# adapter_sch.net
KiCad netlist of a schematic drawn in Altium Designer
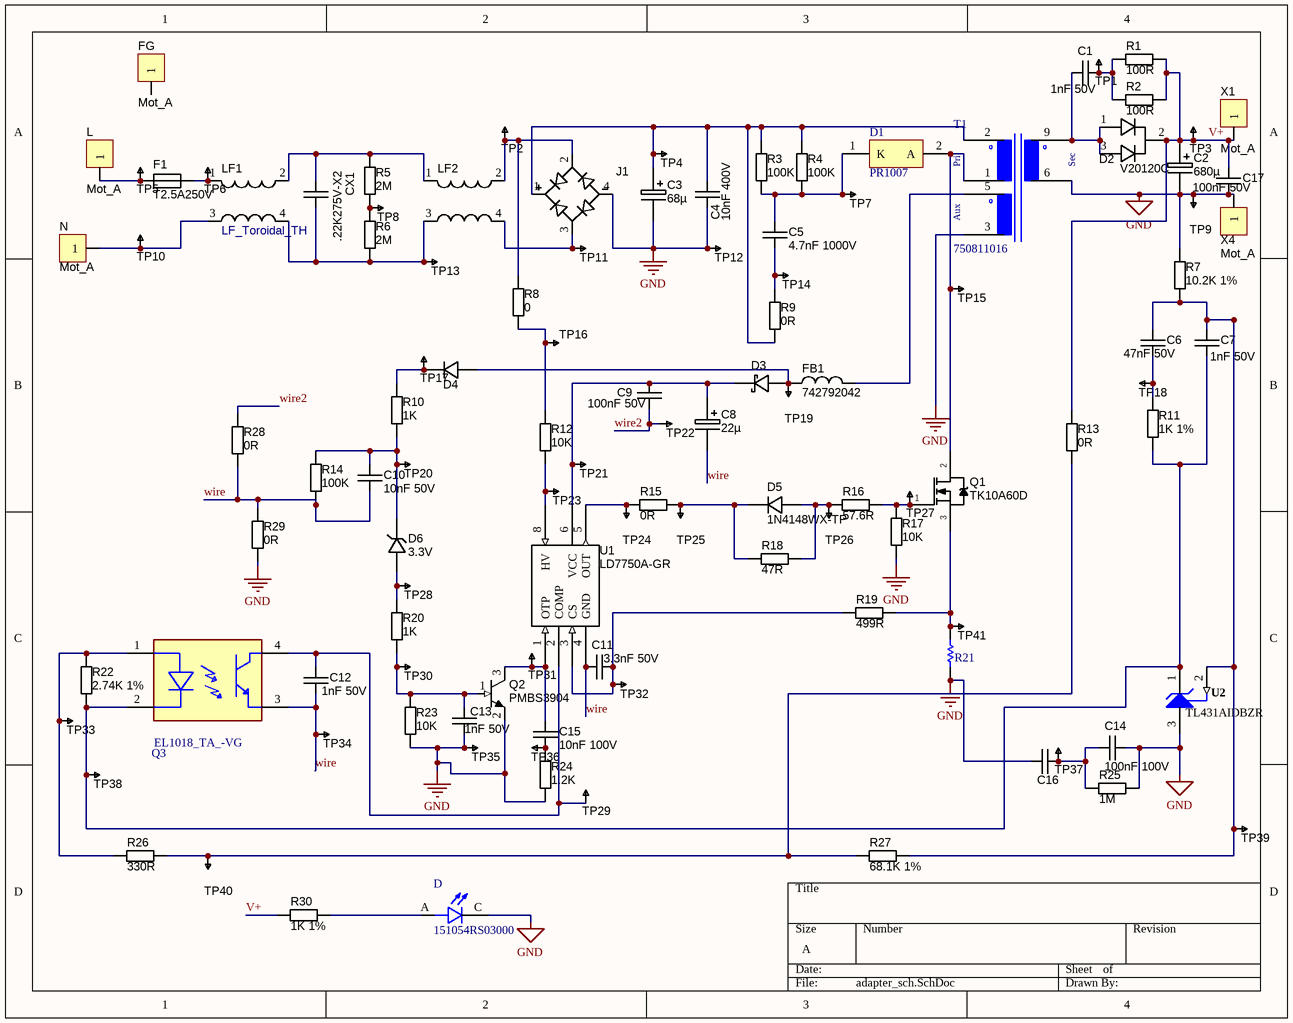
[diagram p0: adapter_sch.SchDoc]

(export (version "E")
  (design (tool "Eeschema 10.0.6"))
  (components
    (comp (ref "C1")
      (value "1nF 50V")
      (footprint "CAPC2012X135N")
      (description "Capacitor SMD Cer 4.7uF 10% 16V X5R 0805")
      (fields (field (name "TOLERANCE") "±10%") (field (name "Comment") "approved sub OK"))
      (libsource (lib "PBL - Capacitors") (part "CAPC_4u7_0805"))
    )
    (comp (ref "C2")
      (value "680µ")
      (footprint "CAPE4.7MM_Rad_10x17mm")
      (description "Capacitor THT Alum Elec 680uF 25V")
      (fields (field (name "TOLERANCE") "±20%"))
      (libsource (lib "PBL - Capacitors") (part "CAPE_680u_25V_THT"))
    )
    (comp (ref "C3")
      (value "68µ")
      (footprint "CAPAE400V68uF16X25")
      (description "Capacitor THT Alum Elec 68uF 20% 400V")
      (fields (field (name "TOLERANCE") "±20%"))
      (libsource (lib "PBL - Capacitors") (part "CAPE_68u_400V_THT"))
    )
    (comp (ref "C4")
      (value "10nF 400V")
      (footprint "CAPC3216X180N")
      (description "Capacitor SMD Cer 10uF 10% 16V X7R 1206")
      (fields (field (name "TOLERANCE") "±10%") (field (name "Comment") "approved sub OK"))
      (libsource (lib "PBL - Capacitors") (part "CAPC_10u_1206_16V"))
    )
    (comp (ref "C5")
      (value "4.7nF 1000V")
      (footprint "CAPC3216X180N")
      (description "Capacitor SMD Cer 10uF 10% 16V X7R 1206")
      (fields (field (name "TOLERANCE") "±10%") (field (name "Comment") "approved sub OK"))
      (libsource (lib "PBL - Capacitors") (part "CAPC_10u_1206_16V"))
    )
    (comp (ref "C6")
      (value "47nF 50V")
      (footprint "CAPC1608X90N")
      (description "Capacitor SMD Cer 10pF 5% 50V NP0 0603")
      (fields (field (name "TOLERANCE") "±5%"))
      (libsource (lib "PBL - Capacitors") (part "CAPC_10p_0603_NP0_1%_50V"))
    )
    (comp (ref "C7")
      (value "1nF 50V")
      (footprint "CAPC1608X90N")
      (description "Capacitor SMD Cer 10pF 5% 50V NP0 0603")
      (fields (field (name "TOLERANCE") "±5%"))
      (libsource (lib "PBL - Capacitors") (part "CAPC_10p_0603_NP0_1%_50V"))
    )
    (comp (ref "C8")
      (value "22µ")
      (footprint "CAPE2MM_Rad_5x11mm")
      (description "Capacitor THT Alum Elec 22uF 50V")
      (fields (field (name "TOLERANCE") "±20%"))
      (libsource (lib "PBL - Capacitors") (part "CAPE_22u_50V_THT"))
    )
    (comp (ref "C9")
      (value "100nF 50V")
      (footprint "CAPC1608X90N")
      (description "Capacitor SMD Cer 10pF 5% 50V NP0 0603")
      (fields (field (name "TOLERANCE") "±5%"))
      (libsource (lib "PBL - Capacitors") (part "CAPC_10p_0603_NP0_1%_50V"))
    )
    (comp (ref "C10")
      (value "10nF 50V")
      (footprint "CAPC1608X90N")
      (description "Capacitor SMD Cer 10pF 5% 50V NP0 0603")
      (fields (field (name "TOLERANCE") "±5%"))
      (libsource (lib "PBL - Capacitors") (part "CAPC_10p_0603_NP0_1%_50V"))
    )
    (comp (ref "C11")
      (value "3.3nF 50V")
      (footprint "CAPC1608X90N")
      (description "Capacitor SMD Cer 10pF 5% 50V NP0 0603")
      (fields (field (name "TOLERANCE") "±5%"))
      (libsource (lib "PBL - Capacitors") (part "CAPC_10p_0603_NP0_1%_50V"))
    )
    (comp (ref "C12")
      (value "1nF 50V")
      (footprint "CAPC1608X90N")
      (description "Capacitor SMD Cer 10pF 5% 50V NP0 0603")
      (fields (field (name "TOLERANCE") "±5%"))
      (libsource (lib "PBL - Capacitors") (part "CAPC_10p_0603_NP0_1%_50V"))
    )
    (comp (ref "C13")
      (value "1nF 50V")
      (footprint "CAPC1608X90N")
      (description "Capacitor SMD Cer 10pF 5% 50V NP0 0603")
      (fields (field (name "TOLERANCE") "±5%"))
      (libsource (lib "PBL - Capacitors") (part "CAPC_10p_0603_NP0_1%_50V"))
    )
    (comp (ref "C14")
      (value "100nF 100V")
      (footprint "CAPC3216X180N")
      (description "Capacitor SMD Cer 10uF 10% 16V X7R 1206")
      (fields (field (name "TOLERANCE") "±10%") (field (name "Comment") "approved sub OK"))
      (libsource (lib "PBL - Capacitors") (part "CAPC_10u_1206_16V"))
    )
    (comp (ref "C15")
      (value "10nF 100V")
      (footprint "CAPC1608X90N")
      (description "Capacitor SMD Cer 10pF 5% 50V NP0 0603")
      (fields (field (name "TOLERANCE") "±5%"))
      (libsource (lib "PBL - Capacitors") (part "CAPC_10p_0603_NP0_1%_50V"))
    )
    (comp (ref "C16")
      (value "~")
      (footprint "CAPR9.5_CC")
      (description "Capacitor THD Ceramic 4KV")
      (fields (field (name "TOLERANCE") "±10%"))
      (libsource (lib "PBL - Capacitors") (part "CAPC_4KVV_CR"))
    )
    (comp (ref "C17")
      (value "100nF 50V")
      (footprint "C0805")
      (description "Capacitor SMD Cer 4.7uF 10% 16V X5R 0805")
      (fields (field (name "TOLERANCE") "±10%") (field (name "Comment") "approved sub OK"))
      (libsource (lib "PBL - Capacitors") (part "CAPC_4u7_0805"))
    )
    (comp (ref "CX1")
      (value ".22K275V-X2")
      (footprint "CAPMPF0.22K275V-X2_0.22UF")
      (description "Safety Capacitor THD MP Film 22nF 10% 250V")
      (fields (field (name "TOLERANCE") "±10%"))
      (libsource (lib "PBL - Capacitors") (part "CAPMPF_22n_250V_MP"))
    )
    (comp (ref "D")
      (value "151054RS03000")
      (footprint "LED_151054RS03000")
      (description "Red 623nm LED Indication - Discrete 1.9V Radial")
      (fields (field (name "MF") "Wurth Electronics"))
      (libsource (lib "LED_Radial151054RS03000") (part "151054RS03000"))
    )
    (comp (ref "D1")
      (value "PR1007")
      (footprint "DO-41 - Bended Radial")
      (description "Fast Recovery Rectifier Diode, 2-Pin Axial_Lead, Pb-Free, Bulk Box")
      (fields (field (name "MANUFACTURER") "On Semiconductor") (field (name "PARTNUMBER") "1N4003FF"))
      (libsource (lib "Diodes") (part "PR1007"))
    )
    (comp (ref "D2")
      (value "DIODE_SCHOTTKY_V20120C_TH")
      (footprint "DIODE_SCHOTTKY_V20120C_TH")
      (description "SCHOTTKY RECTIFIER TO-220AB COMMON CATHODE THROUGH HOLE")
      (fields
        (field (name "MANUFACTURER") "Micro Commercial Co")
        (field (name "MANUFACTURER PART NUMBER") "V20120C")
      )
      (libsource (lib "PBL - Diodes") (part "DIODE_SCHOTTKY_V20120C_TH"))
    )
    (comp (ref "D3")
      (value "DIODE_SCHOTTKY_10MQ100NPBF")
      (footprint "DO-214AC")
      (description "Diode Schottky SMD 100V 2A SMA")
      (libsource (lib "PBL - Diodes") (part "DIODE_SCHOTTKY_10MQ100NPBF"))
    )
    (comp (ref "D4")
      (value "100V; 1.5A")
      (footprint "SOD123")
      (description "surface mount switching diode L1N4148WT1G")
      (libsource (lib "PBL - Diodes") (part "DIODE_switching_SJ_SOD_1-3"))
    )
    (comp (ref "D5")
      (value "DIODE_75V_500mW")
      (footprint "SOD323")
      (description "Diode SMD 300mA 0.5W SOD323")
      (fields
        (field (name "MANUFACTURER") "Micro Commercial Co")
        (field (name "MANUFACTURER PART NUMBER") "1N4148WX-TP")
      )
      (libsource (lib "PBL - Diodes") (part "DIODE_75V_500mW"))
    )
    (comp (ref "D6")
      (value "3.3V")
      (footprint "SOD323")
      (description "Diode Zener SMD 3.3V 200mW SOD-323")
      (fields (field (name "TOLERANCE") "±3%"))
      (libsource (lib "PBL - Diodes") (part "DIODE_ZENER_3V3_SOD323"))
    )
    (comp (ref "F1")
      (value "T2.5A250V")
      (footprint "FUSE_MST250")
      (description "Radial Lead Micro Fuse, 2.5A TH")
      (fields (field (name "Comment") "Radial Lead Micro Fuse, 2.5A"))
      (libsource (lib "PBL - Fuses and Protection") (part "FUSE_MST_2.5A_250V"))
    )
    (comp (ref "FB1")
      (value "600R @ 100 MHz")
      (footprint "FBC2012N")
      (description "Ferrite bead Wurth 742792042 SMD 200mA 0805")
      (fields (field (name "MANUFACTURER PART NUMBER 1") "742792042"))
      (libsource (lib "PBL - Inductors") (part "FERRITE_WURTH_742792042"))
    )
    (comp (ref "FG")
      (value "Mot_A")
      (footprint "THP_D38_T75_B125")
      (libsource (lib "PBL - Pads and Jumpers") (part "Term1"))
    )
    (comp (ref "J1")
      (value "100V; 1.5A")
      (footprint "BR_KBP208GL")
      (description "KBP208GL GLASS PASSIVATED BRIDGE RECTIFIER")
      (libsource (lib "PBL - Diodes") (part "BR_KBP208GL_TH"))
    )
    (comp (ref "L")
      (value "Mot_A")
      (footprint "THP_D38_T75_B125")
      (libsource (lib "PBL - Pads and Jumpers") (part "Term1"))
    )
    (comp (ref "LF1")
      (value "LF_Toroidal_TH")
      (footprint "LF_Toroidal_TH")
      (description "Toroidal line filter common-mode choke TH")
      (libsource (lib "PBL - Inductors") (part "LF_Toroidal_TH"))
    )
    (comp (ref "LF2")
      (value "LF_AC_Common_Mode_Ferrite_magnet_Coil")
      (footprint "LF_AC_Common_Mode_Ferrite_magnet_Coil")
      (description "AC Common Mode Ferrite magnet Chokes")
      (libsource (lib "PBL - Inductors") (part "LF_AC_Common_Mode_Ferrite_magnet_Coil"))
    )
    (comp (ref "N") (value "Mot_A") (footprint "THP_D38_T75_B125") (libsource (lib "") (part "Term1_2")))
    (comp (ref "Q1")
      (value "TK10A60D")
      (footprint "MOS_TK10A60E")
      (description "MOSFET N-Channel Power Switching TH")
      (fields (field (name "MANUFACTURER PART NUMBER 1") "TK10A60D"))
      (libsource (lib "PBL - Transistors") (part "MOSFET_N-CH_TK10A60D"))
    )
    (comp (ref "Q2")
      (value "PMBS3904")
      (footprint "SOT23-3")
      (description "Transistor SMD NPN 40V 100mA 250mW SOT23")
      (libsource (lib "PBL - Transistors") (part "NPN_PMBS3904_PHILIPS"))
    )
    (comp (ref "Q3")
      (value "EL1018_TA_-VG")
      (footprint "SOP4_Everlight_EL101X-G_MFG")
      (libsource (lib "PBL - Optical Components") (part "EL1018_TA_-VG"))
    )
    (comp (ref "R1")
      (value "100R")
      (footprint "RESC3216X70N")
      (description "Resistor, SMD chip")
      (fields (field (name "Comment") "RES_NL_1206"))
      (libsource (lib "") (part "RES_NL_1206_1"))
    )
    (comp (ref "R2")
      (value "100R")
      (footprint "RESC3216X70N")
      (description "Resistor, SMD chip")
      (fields (field (name "Comment") "RES_NL_1206"))
      (libsource (lib "") (part "RES_NL_1206_1"))
    )
    (comp (ref "R3")
      (value "100K")
      (footprint "RESC3216X70N")
      (description "Resistor, SMD chip")
      (fields (field (name "Comment") "RES_NL_1206"))
      (libsource (lib "PBL - Resistors") (part "RES_NL_1206"))
    )
    (comp (ref "R4")
      (value "100K")
      (footprint "RESC3216X70N")
      (description "Resistor, SMD chip")
      (fields (field (name "Comment") "RES_NL_1206"))
      (libsource (lib "PBL - Resistors") (part "RES_NL_1206"))
    )
    (comp (ref "R5")
      (value "2M")
      (footprint "RESC3216X70N")
      (description "Resistor, SMD chip")
      (fields (field (name "Comment") "RES_NL_1206"))
      (libsource (lib "PBL - Resistors") (part "RES_NL_1206"))
    )
    (comp (ref "R6")
      (value "2M")
      (footprint "RESC3216X70N")
      (description "Resistor, SMD chip")
      (fields (field (name "Comment") "RES_NL_1206"))
      (libsource (lib "PBL - Resistors") (part "RES_NL_1206"))
    )
    (comp (ref "R7")
      (value "10.2K 1%")
      (footprint "RESC1608X55N")
      (description "Resistor, SMD chip")
      (fields (field (name "Comment") "RES_NL_0603"))
      (libsource (lib "PBL - Resistors") (part "RES_NL_0603"))
    )
    (comp (ref "R8")
      (value "0")
      (footprint "RESC3216X70N")
      (description "Resistor, SMD chip")
      (fields (field (name "Comment") "RES_NL_1206"))
      (libsource (lib "PBL - Resistors") (part "RES_NL_1206"))
    )
    (comp (ref "R9")
      (value "0R")
      (footprint "RESC3216N_ZERO")
      (description "Resistor SMD chip 0.0 Ohm 0.25W 1206")
      (fields (field (name "TOLERANCE") "±5%") (field (name "Comment") "Thick Film"))
      (libsource (lib "PBL - Resistors") (part "RES_0R_1206"))
    )
    (comp (ref "R10")
      (value "1K")
      (footprint "RESC1608X55N")
      (description "Resistor, SMD chip")
      (fields (field (name "Comment") "RES_NL_0603"))
      (libsource (lib "PBL - Resistors") (part "RES_NL_0603"))
    )
    (comp (ref "R11")
      (value "1K 1%")
      (footprint "RESC1608X55N")
      (description "Resistor, SMD chip")
      (fields (field (name "Comment") "RES_NL_0603"))
      (libsource (lib "PBL - Resistors") (part "RES_NL_0603"))
    )
    (comp (ref "R12")
      (value "10K")
      (footprint "RESC3216X70N")
      (description "Resistor, SMD chip")
      (fields (field (name "Comment") "RES_NL_1206"))
      (libsource (lib "PBL - Resistors") (part "RES_NL_1206"))
    )
    (comp (ref "R13")
      (value "0R")
      (footprint "RESC2012N_ZERO")
      (description "Resistor SMD chip 0.0 Ohm 0.125W 0805")
      (fields (field (name "Comment") "Jumper"))
      (libsource (lib "PBL - Resistors") (part "RES_0R_0805"))
    )
    (comp (ref "R14")
      (value "100K")
      (footprint "RESC1608X55N")
      (description "Resistor, SMD chip")
      (fields (field (name "Comment") "RES_NL_0603"))
      (libsource (lib "PBL - Resistors") (part "RES_NL_0603"))
    )
    (comp (ref "R15")
      (value "0R")
      (footprint "RESC2012X70N")
      (description "Resistor SMD chip 0.0 Ohm 0.25W 1206")
      (fields (field (name "TOLERANCE") "±5%") (field (name "Comment") "Thick Film"))
      (libsource (lib "") (part "RES_0R_1206_1"))
    )
    (comp (ref "R16")
      (value "57.6R")
      (footprint "AXIAL-0.6-17.5mm")
      (description "Resistor THD 10 Ohm 1W 5% Metal Film")
      (fields (field (name "TOLERANCE") "±5%") (field (name "Comment") "Metal Film"))
      (libsource (lib "PBL - Resistors") (part "RES_10R_Axial_1W_5%"))
    )
    (comp (ref "R17")
      (value "10K")
      (footprint "RESC1608X55N")
      (description "Resistor, SMD chip")
      (fields (field (name "Comment") "RES_NL_0603"))
      (libsource (lib "PBL - Resistors") (part "RES_NL_0603"))
    )
    (comp (ref "R18")
      (value "47R")
      (footprint "RESC2012X70N")
      (description "Resistor, SMD chip")
      (fields (field (name "Comment") "RES_NL_0805"))
      (libsource (lib "PBL - Resistors") (part "RES_NL_0805"))
    )
    (comp (ref "R19")
      (value "499R")
      (footprint "RESC1608X55N")
      (description "Resistor, SMD chip")
      (fields (field (name "Comment") "RES_NL_0603"))
      (libsource (lib "") (part "RES_NL_0603_1"))
    )
    (comp (ref "R20")
      (value "1K")
      (footprint "RESC2012X70N")
      (description "Resistor, SMD chip")
      (fields (field (name "Comment") "RES_NL_0805"))
      (libsource (lib "") (part "RES_NL_0805_1"))
    )
    (comp (ref "R21")
      (value "Res_Com_radial_bended")
      (footprint "R1/4WD - p4.8")
      (description "4.59K +/-0.5%")
      (libsource (lib "Resistors_SMD_IPC-SM-782") (part "Res_Com_radial_bended"))
    )
    (comp (ref "R22")
      (value "2.74K 1%")
      (footprint "RESC1608X55N")
      (description "Resistor, SMD chip")
      (fields (field (name "Comment") "RES_NL_0603"))
      (libsource (lib "PBL - Resistors") (part "RES_NL_0603"))
    )
    (comp (ref "R23")
      (value "10K")
      (footprint "RESC1608X55N")
      (description "Resistor, SMD chip")
      (fields (field (name "Comment") "RES_NL_0603"))
      (libsource (lib "PBL - Resistors") (part "RES_NL_0603"))
    )
    (comp (ref "R24")
      (value "1.2K")
      (footprint "RESC1608X55N")
      (description "Resistor, SMD chip")
      (fields (field (name "Comment") "RES_NL_0603"))
      (libsource (lib "PBL - Resistors") (part "RES_NL_0603"))
    )
    (comp (ref "R25")
      (value "1M")
      (footprint "RESC3216X70N")
      (description "Resistor, SMD chip")
      (fields (field (name "Comment") "RES_NL_1206"))
      (libsource (lib "") (part "RES_NL_1206_1"))
    )
    (comp (ref "R26")
      (value "330R")
      (footprint "RESC3216X70N")
      (description "Resistor, SMD chip")
      (fields (field (name "Comment") "RES_NL_1206"))
      (libsource (lib "") (part "RES_NL_1206_1"))
    )
    (comp (ref "R27")
      (value "68.1K 1%")
      (footprint "RESC1608X55N")
      (description "Resistor, SMD chip")
      (fields (field (name "Comment") "RES_NL_0603"))
      (libsource (lib "") (part "RES_NL_0603_1"))
    )
    (comp (ref "R28")
      (value "0R")
      (footprint "RESC3216X70N")
      (description "Resistor SMD chip 0.0 Ohm 0.25W 1206")
      (fields (field (name "TOLERANCE") "±5%") (field (name "Comment") "Thick Film"))
      (libsource (lib "PBL - Resistors") (part "RES_0R_1206"))
    )
    (comp (ref "R29")
      (value "0R")
      (footprint "RESC3216N_ZERO")
      (description "Resistor SMD chip 0.0 Ohm 0.25W 1206")
      (fields (field (name "TOLERANCE") "±5%") (field (name "Comment") "Thick Film"))
      (libsource (lib "PBL - Resistors") (part "RES_0R_1206"))
    )
    (comp (ref "R30")
      (value "1K 1%")
      (footprint "RESC1608X55N")
      (description "Resistor, SMD chip")
      (fields (field (name "Comment") "RES_NL_0603"))
      (libsource (lib "") (part "RES_NL_0603_1"))
    )
    (comp (ref "T1")
      (value "750811016")
      (footprint "Transformer_THT_H_7PIN")
      (description "Flyback Converters For For AC/DC Converters SMPS Transformer 4500Vrms Isolation Through Hole")
      (fields (field (name "MF") "Wurth Electronics"))
      (libsource (lib "SnapEDAsch") (part "750811016"))
    )
    (comp (ref "TP1")
      (value "TESTPOINT")
      (footprint "TP-R60")
      (description "SMD test pin")
      (libsource (lib "PBL - Test Points") (part "TESTPOINT"))
    )
    (comp (ref "TP2")
      (value "TESTPOINT")
      (footprint "TP-R60")
      (description "SMD test pin")
      (libsource (lib "PBL - Test Points") (part "TESTPOINT"))
    )
    (comp (ref "TP3")
      (value "TESTPOINT")
      (footprint "TP-R60")
      (description "SMD test pin")
      (libsource (lib "PBL - Test Points") (part "TESTPOINT"))
    )
    (comp (ref "TP4")
      (value "TESTPOINT")
      (footprint "TP-R60")
      (description "SMD test pin")
      (libsource (lib "PBL - Test Points") (part "TESTPOINT"))
    )
    (comp (ref "TP5")
      (value "TESTPOINT")
      (footprint "TP-R60")
      (description "SMD test pin")
      (libsource (lib "PBL - Test Points") (part "TESTPOINT"))
    )
    (comp (ref "TP6")
      (value "TESTPOINT")
      (footprint "TP-R60")
      (description "SMD test pin")
      (libsource (lib "PBL - Test Points") (part "TESTPOINT"))
    )
    (comp (ref "TP7")
      (value "TESTPOINT")
      (footprint "TP-R60")
      (description "SMD test pin")
      (libsource (lib "PBL - Test Points") (part "TESTPOINT"))
    )
    (comp (ref "TP8")
      (value "TESTPOINT")
      (footprint "TP-R60")
      (description "SMD test pin")
      (libsource (lib "PBL - Test Points") (part "TESTPOINT"))
    )
    (comp (ref "TP9")
      (value "TESTPOINT")
      (footprint "TP-R60")
      (description "SMD test pin")
      (libsource (lib "PBL - Test Points") (part "TESTPOINT"))
    )
    (comp (ref "TP10")
      (value "TESTPOINT")
      (footprint "TP-R60")
      (description "SMD test pin")
      (libsource (lib "PBL - Test Points") (part "TESTPOINT"))
    )
    (comp (ref "TP11")
      (value "TESTPOINT")
      (footprint "TP-R60")
      (description "SMD test pin")
      (libsource (lib "PBL - Test Points") (part "TESTPOINT"))
    )
    (comp (ref "TP12")
      (value "TESTPOINT")
      (footprint "TP-R60")
      (description "SMD test pin")
      (libsource (lib "PBL - Test Points") (part "TESTPOINT"))
    )
    (comp (ref "TP13")
      (value "TESTPOINT")
      (footprint "TP-R60")
      (description "SMD test pin")
      (libsource (lib "PBL - Test Points") (part "TESTPOINT"))
    )
    (comp (ref "TP14")
      (value "TESTPOINT")
      (footprint "TP-R60")
      (description "SMD test pin")
      (libsource (lib "PBL - Test Points") (part "TESTPOINT"))
    )
    (comp (ref "TP15")
      (value "TESTPOINT")
      (footprint "TP-R60")
      (description "SMD test pin")
      (libsource (lib "PBL - Test Points") (part "TESTPOINT"))
    )
    (comp (ref "TP16")
      (value "TESTPOINT")
      (footprint "TP-R60")
      (description "SMD test pin")
      (libsource (lib "PBL - Test Points") (part "TESTPOINT"))
    )
    (comp (ref "TP17")
      (value "TESTPOINT")
      (footprint "TP-R60")
      (description "SMD test pin")
      (libsource (lib "PBL - Test Points") (part "TESTPOINT"))
    )
    (comp (ref "TP18")
      (value "TESTPOINT")
      (footprint "TP-R60")
      (description "SMD test pin")
      (libsource (lib "PBL - Test Points") (part "TESTPOINT"))
    )
    (comp (ref "TP19")
      (value "TESTPOINT")
      (footprint "TP-R60")
      (description "SMD test pin")
      (libsource (lib "PBL - Test Points") (part "TESTPOINT"))
    )
    (comp (ref "TP20")
      (value "TESTPOINT")
      (footprint "TP-R60")
      (description "SMD test pin")
      (libsource (lib "PBL - Test Points") (part "TESTPOINT"))
    )
    (comp (ref "TP21")
      (value "TESTPOINT")
      (footprint "TP-R60")
      (description "SMD test pin")
      (libsource (lib "PBL - Test Points") (part "TESTPOINT"))
    )
    (comp (ref "TP22")
      (value "TESTPOINT")
      (footprint "TP-R60")
      (description "SMD test pin")
      (libsource (lib "PBL - Test Points") (part "TESTPOINT"))
    )
    (comp (ref "TP23")
      (value "TESTPOINT")
      (footprint "TP-R60")
      (description "SMD test pin")
      (libsource (lib "PBL - Test Points") (part "TESTPOINT"))
    )
    (comp (ref "TP24")
      (value "TESTPOINT")
      (footprint "TP-R60")
      (description "SMD test pin")
      (libsource (lib "PBL - Test Points") (part "TESTPOINT"))
    )
    (comp (ref "TP25")
      (value "TESTPOINT")
      (footprint "TP-R60")
      (description "SMD test pin")
      (libsource (lib "PBL - Test Points") (part "TESTPOINT"))
    )
    (comp (ref "TP26")
      (value "TESTPOINT")
      (footprint "TP-R60")
      (description "SMD test pin")
      (libsource (lib "PBL - Test Points") (part "TESTPOINT"))
    )
    (comp (ref "TP27")
      (value "TESTPOINT")
      (footprint "TP-R60")
      (description "SMD test pin")
      (libsource (lib "PBL - Test Points") (part "TESTPOINT"))
    )
    (comp (ref "TP28")
      (value "TESTPOINT")
      (footprint "TP-R60")
      (description "SMD test pin")
      (libsource (lib "PBL - Test Points") (part "TESTPOINT"))
    )
    (comp (ref "TP29")
      (value "TESTPOINT")
      (footprint "TP-R60")
      (description "SMD test pin")
      (libsource (lib "PBL - Test Points") (part "TESTPOINT"))
    )
    (comp (ref "TP30")
      (value "TESTPOINT")
      (footprint "TP-R60")
      (description "SMD test pin")
      (libsource (lib "PBL - Test Points") (part "TESTPOINT"))
    )
    (comp (ref "TP31")
      (value "TESTPOINT")
      (footprint "TP-R60")
      (description "SMD test pin")
      (libsource (lib "PBL - Test Points") (part "TESTPOINT"))
    )
    (comp (ref "TP32")
      (value "TESTPOINT")
      (footprint "TP-R60")
      (description "SMD test pin")
      (libsource (lib "PBL - Test Points") (part "TESTPOINT"))
    )
    (comp (ref "TP33")
      (value "TESTPOINT")
      (footprint "TP-R60")
      (description "SMD test pin")
      (libsource (lib "PBL - Test Points") (part "TESTPOINT"))
    )
    (comp (ref "TP34")
      (value "TESTPOINT")
      (footprint "TP-R60")
      (description "SMD test pin")
      (libsource (lib "PBL - Test Points") (part "TESTPOINT"))
    )
    (comp (ref "TP35")
      (value "TESTPOINT")
      (footprint "TP-R60")
      (description "SMD test pin")
      (libsource (lib "PBL - Test Points") (part "TESTPOINT"))
    )
    (comp (ref "TP36")
      (value "TESTPOINT")
      (footprint "TP-R60")
      (description "SMD test pin")
      (libsource (lib "PBL - Test Points") (part "TESTPOINT"))
    )
    (comp (ref "TP37")
      (value "TESTPOINT")
      (footprint "TP-R60")
      (description "SMD test pin")
      (libsource (lib "PBL - Test Points") (part "TESTPOINT"))
    )
    (comp (ref "TP38")
      (value "TESTPOINT")
      (footprint "TP-R60")
      (description "SMD test pin")
      (libsource (lib "PBL - Test Points") (part "TESTPOINT"))
    )
    (comp (ref "TP39")
      (value "TESTPOINT")
      (footprint "TP-R60")
      (description "SMD test pin")
      (libsource (lib "PBL - Test Points") (part "TESTPOINT"))
    )
    (comp (ref "TP40")
      (value "TESTPOINT")
      (footprint "TP-R60")
      (description "SMD test pin")
      (libsource (lib "PBL - Test Points") (part "TESTPOINT"))
    )
    (comp (ref "TP41")
      (value "TESTPOINT")
      (footprint "TP-R60")
      (description "SMD test pin")
      (libsource (lib "PBL - Test Points") (part "TESTPOINT"))
    )
    (comp (ref "U1")
      (value "LD7750A-GR")
      (footprint "SOP7_LD7750AGR")
      (description "PWM CONTROLLER LD7750AGR SOP-7")
      (libsource (lib "PBL - Integrated Circuits") (part "PWM_CONT_LD7750A-GR"))
    )
    (comp (ref "U2")
      (value "TL431AIDBZR")
      (footprint "SOT23_L")
      (fields (field (name "MANUFACTURER") "Texas Instruments"))
      (libsource (lib "PBL - Integrated Circuits") (part "TL431AIDBZR"))
    )
    (comp (ref "X1")
      (value "Mot_A")
      (footprint "THP_D38_T75_B125")
      (libsource (lib "PBL - Pads and Jumpers") (part "Term1"))
    )
    (comp (ref "X4") (value "Mot_A") (footprint "THP_D38_T75_B125") (libsource (lib "") (part "Term1_1")))
  )
  (nets
    (net (code "1") (name "/V+") (class "Default")
      (node (ref "C17") (pin "2") (pintype "passive"))
      (node (ref "C2") (pin "1") (pintype "passive"))
      (node (ref "D2") (pin "2") (pinfunction "K_2") (pintype "passive"))
      (node (ref "R1") (pin "2") (pinfunction "2_2") (pintype "passive"))
      (node (ref "R13") (pin "1") (pinfunction "1_1") (pintype "passive"))
      (node (ref "R2") (pin "2") (pinfunction "2_2") (pintype "passive"))
      (node (ref "R30") (pin "1") (pinfunction "1_1") (pintype "passive"))
      (node (ref "TP3") (pin "1") (pintype "passive"))
      (node (ref "X1") (pin "1") (pinfunction "1_1") (pintype "passive"))
    )
    (net (code "2") (name "/wire") (class "Default")
      (node (ref "C10") (pin "2") (pintype "passive"))
      (node (ref "C11") (pin "1") (pintype "passive"))
      (node (ref "C12") (pin "2") (pintype "passive"))
      (node (ref "C8") (pin "2") (pintype "passive"))
      (node (ref "Q3") (pin "3") (pinfunction "E_3") (pintype "passive"))
      (node (ref "R14") (pin "2") (pinfunction "2_2") (pintype "passive"))
      (node (ref "R28") (pin "2") (pinfunction "2_2") (pintype "passive"))
      (node (ref "R29") (pin "1") (pinfunction "1_1") (pintype "passive"))
      (node (ref "TP34") (pin "1") (pintype "passive"))
      (node (ref "U1") (pin "4") (pinfunction "GND_4") (pintype "power_in"))
    )
    (net (code "3") (name "/wire2") (class "Default")
      (node (ref "C9") (pin "2") (pintype "passive"))
      (node (ref "R28") (pin "1") (pinfunction "1_1") (pintype "passive"))
      (node (ref "TP22") (pin "1") (pintype "passive"))
    )
    (net (code "4") (name "GND") (class "Default")
      (node (ref "C13") (pin "2") (pintype "passive"))
      (node (ref "C14") (pin "2") (pintype "passive"))
      (node (ref "C16") (pin "1") (pintype "passive"))
      (node (ref "C17") (pin "1") (pintype "passive"))
      (node (ref "C2") (pin "2") (pintype "passive"))
      (node (ref "C3") (pin "2") (pintype "passive"))
      (node (ref "C4") (pin "2") (pintype "passive"))
      (node (ref "D") (pin "C") (pinfunction "C_C") (pintype "passive"))
      (node (ref "J1") (pin "4") (pinfunction "NEG_4") (pintype "passive"))
      (node (ref "Q2") (pin "2") (pinfunction "E_2") (pintype "passive"))
      (node (ref "R17") (pin "2") (pinfunction "2_2") (pintype "passive"))
      (node (ref "R21") (pin "1") (pinfunction "1_1") (pintype "passive"))
      (node (ref "R23") (pin "2") (pinfunction "2_2") (pintype "passive"))
      (node (ref "R24") (pin "2") (pinfunction "2_2") (pintype "passive"))
      (node (ref "R25") (pin "2") (pinfunction "2_2") (pintype "passive"))
      (node (ref "R29") (pin "2") (pinfunction "2_2") (pintype "passive"))
      (node (ref "R7") (pin "1") (pinfunction "1_1") (pintype "passive"))
      (node (ref "T1") (pin "3") (pinfunction "3_3") (pintype "passive"))
      (node (ref "T1") (pin "6") (pinfunction "6_6") (pintype "passive"))
      (node (ref "TP12") (pin "1") (pintype "passive"))
      (node (ref "TP35") (pin "1") (pintype "passive"))
      (node (ref "TP9") (pin "1") (pintype "passive"))
      (node (ref "U2") (pin "3") (pinfunction "ANODE_3") (pintype "passive"))
      (node (ref "X4") (pin "1") (pinfunction "1_1") (pintype "passive"))
    )
    (net (code "5") (name "Net-(C1-Pad1)") (class "Default")
      (node (ref "C1") (pin "1") (pintype "passive"))
      (node (ref "D2") (pin "1") (pinfunction "A_1") (pintype "passive"))
      (node (ref "D2") (pin "3") (pinfunction "A_3") (pintype "passive"))
      (node (ref "T1") (pin "9") (pinfunction "9_9") (pintype "passive"))
    )
    (net (code "6") (name "Net-(C1-Pad2)") (class "Default")
      (node (ref "C1") (pin "2") (pintype "passive"))
      (node (ref "R1") (pin "1") (pinfunction "1_1") (pintype "passive"))
      (node (ref "R2") (pin "1") (pinfunction "1_1") (pintype "passive"))
      (node (ref "TP1") (pin "1") (pintype "passive"))
    )
    (net (code "7") (name "Net-(C5-Pad2)") (class "Default")
      (node (ref "C5") (pin "2") (pintype "passive"))
      (node (ref "R9") (pin "1") (pinfunction "1_1") (pintype "passive"))
      (node (ref "TP14") (pin "1") (pintype "passive"))
    )
    (net (code "8") (name "Net-(C6-Pad2)") (class "Default")
      (node (ref "C6") (pin "2") (pintype "passive"))
      (node (ref "R11") (pin "1") (pinfunction "1_1") (pintype "passive"))
      (node (ref "TP18") (pin "1") (pintype "passive"))
    )
    (net (code "9") (name "Net-(C10-Pad1)") (class "Default")
      (node (ref "C10") (pin "1") (pintype "passive"))
      (node (ref "D6") (pin "K") (pinfunction "K_K") (pintype "passive"))
      (node (ref "R10") (pin "2") (pinfunction "2_2") (pintype "passive"))
      (node (ref "R14") (pin "1") (pinfunction "1_1") (pintype "passive"))
      (node (ref "TP20") (pin "1") (pintype "passive"))
    )
    (net (code "10") (name "Net-(C14-Pad1)") (class "Default")
      (node (ref "C14") (pin "1") (pintype "passive"))
      (node (ref "C16") (pin "2") (pintype "passive"))
      (node (ref "R25") (pin "1") (pinfunction "1_1") (pintype "passive"))
      (node (ref "TP37") (pin "1") (pintype "passive"))
    )
    (net (code "11") (name "Net-(C15-Pad2)") (class "Default")
      (node (ref "C15") (pin "2") (pintype "passive"))
      (node (ref "R24") (pin "1") (pinfunction "1_1") (pintype "passive"))
      (node (ref "TP36") (pin "1") (pintype "passive"))
    )
    (net (code "12") (name "Net-(CX1-Pad1)") (class "Default")
      (node (ref "CX1") (pin "1") (pintype "passive"))
      (node (ref "LF1") (pin "2") (pinfunction "2_2") (pintype "passive"))
      (node (ref "LF2") (pin "1") (pinfunction "1_1") (pintype "passive"))
      (node (ref "R5") (pin "1") (pinfunction "1_1") (pintype "passive"))
    )
    (net (code "13") (name "Net-(CX1-Pad2)") (class "Default")
      (node (ref "CX1") (pin "2") (pintype "passive"))
      (node (ref "LF1") (pin "4") (pinfunction "4_4") (pintype "passive"))
      (node (ref "LF2") (pin "3") (pinfunction "3_3") (pintype "passive"))
      (node (ref "R6") (pin "2") (pinfunction "2_2") (pintype "passive"))
      (node (ref "TP13") (pin "1") (pintype "passive"))
    )
    (net (code "14") (name "Net-(D-PadA)") (class "Default")
      (node (ref "D") (pin "A") (pinfunction "A_A") (pintype "passive"))
      (node (ref "R30") (pin "2") (pinfunction "2_2") (pintype "passive"))
    )
    (net (code "15") (name "Net-(D1-A)") (class "Default")
      (node (ref "D1") (pin "2") (pinfunction "A_2") (pintype "passive"))
      (node (ref "Q1") (pin "2") (pinfunction "D_2") (pintype "passive"))
      (node (ref "T1") (pin "1") (pinfunction "1_1") (pintype "passive"))
      (node (ref "TP15") (pin "1") (pintype "passive"))
    )
    (net (code "16") (name "Net-(D1-K)") (class "Default")
      (node (ref "C5") (pin "1") (pintype "passive"))
      (node (ref "D1") (pin "1") (pinfunction "K_1") (pintype "passive"))
      (node (ref "R3") (pin "2") (pinfunction "2_2") (pintype "passive"))
      (node (ref "R4") (pin "2") (pinfunction "2_2") (pintype "passive"))
      (node (ref "TP7") (pin "1") (pintype "passive"))
    )
    (net (code "17") (name "Net-(D3-PadA)") (class "Default")
      (node (ref "D3") (pin "A") (pinfunction "A_A") (pintype "passive"))
      (node (ref "D4") (pin "A") (pinfunction "A_A") (pintype "passive"))
      (node (ref "FB1") (pin "1") (pinfunction "1_1") (pintype "passive"))
      (node (ref "TP19") (pin "1") (pintype "passive"))
    )
    (net (code "18") (name "Net-(D4-PadK)") (class "Default")
      (node (ref "D4") (pin "K") (pinfunction "K_K") (pintype "passive"))
      (node (ref "R10") (pin "1") (pinfunction "1_1") (pintype "passive"))
      (node (ref "TP17") (pin "1") (pintype "passive"))
    )
    (net (code "19") (name "Net-(D5-PadA)") (class "Default")
      (node (ref "D5") (pin "A") (pinfunction "A_A") (pintype "passive"))
      (node (ref "R16") (pin "1") (pinfunction "1_1") (pintype "passive"))
      (node (ref "R18") (pin "2") (pinfunction "2_2") (pintype "passive"))
      (node (ref "TP26") (pin "1") (pintype "passive"))
    )
    (net (code "20") (name "Net-(D5-PadK)") (class "Default")
      (node (ref "D5") (pin "K") (pinfunction "K_K") (pintype "passive"))
      (node (ref "R15") (pin "1") (pinfunction "1_1") (pintype "passive"))
      (node (ref "R18") (pin "1") (pinfunction "1_1") (pintype "passive"))
      (node (ref "TP25") (pin "1") (pintype "passive"))
    )
    (net (code "21") (name "Net-(D6-PadA)") (class "Default")
      (node (ref "D6") (pin "A") (pinfunction "A_A") (pintype "passive"))
      (node (ref "R20") (pin "2") (pinfunction "2_2") (pintype "passive"))
      (node (ref "TP28") (pin "1") (pintype "passive"))
    )
    (net (code "22") (name "Net-(F1-Pad1)") (class "Default")
      (node (ref "F1") (pin "1") (pinfunction "1_1") (pintype "passive"))
      (node (ref "L") (pin "1") (pinfunction "1_1") (pintype "passive"))
      (node (ref "TP5") (pin "1") (pintype "passive"))
    )
    (net (code "23") (name "Net-(F1-Pad2)") (class "Default")
      (node (ref "F1") (pin "2") (pinfunction "2_2") (pintype "passive"))
      (node (ref "LF1") (pin "1") (pinfunction "1_1") (pintype "passive"))
      (node (ref "TP6") (pin "1") (pintype "passive"))
    )
    (net (code "24") (name "Net-(FB1-Pad2)") (class "Default")
      (node (ref "FB1") (pin "2") (pinfunction "2_2") (pintype "passive"))
      (node (ref "T1") (pin "5") (pinfunction "5_5") (pintype "passive"))
    )
    (net (code "25") (name "Net-(J1-AC1)") (class "Default")
      (node (ref "J1") (pin "2") (pinfunction "AC1_2") (pintype "passive"))
      (node (ref "LF2") (pin "2") (pinfunction "2_2") (pintype "passive"))
      (node (ref "R8") (pin "1") (pinfunction "1_1") (pintype "passive"))
      (node (ref "TP2") (pin "1") (pintype "passive"))
    )
    (net (code "26") (name "Net-(J1-AC2)") (class "Default")
      (node (ref "J1") (pin "3") (pinfunction "AC2_3") (pintype "passive"))
      (node (ref "LF2") (pin "4") (pinfunction "4_4") (pintype "passive"))
      (node (ref "TP11") (pin "1") (pintype "passive"))
    )
    (net (code "27") (name "Net-(J1-POS)") (class "Default")
      (node (ref "C3") (pin "1") (pintype "passive"))
      (node (ref "C4") (pin "1") (pintype "passive"))
      (node (ref "J1") (pin "1") (pinfunction "POS_1") (pintype "passive"))
      (node (ref "R3") (pin "1") (pinfunction "1_1") (pintype "passive"))
      (node (ref "R4") (pin "1") (pinfunction "1_1") (pintype "passive"))
      (node (ref "R9") (pin "2") (pinfunction "2_2") (pintype "passive"))
      (node (ref "T1") (pin "2") (pinfunction "2_2") (pintype "passive"))
      (node (ref "TP4") (pin "1") (pintype "passive"))
    )
    (net (code "28") (name "Net-(LF1-Pad3)") (class "Default")
      (node (ref "LF1") (pin "3") (pinfunction "3_3") (pintype "passive"))
      (node (ref "N") (pin "1") (pinfunction "1_1") (pintype "passive"))
      (node (ref "TP10") (pin "1") (pintype "passive"))
    )
    (net (code "29") (name "Net-(Q1-G)") (class "Default")
      (node (ref "Q1") (pin "1") (pinfunction "G_1") (pintype "passive"))
      (node (ref "R16") (pin "2") (pinfunction "2_2") (pintype "passive"))
      (node (ref "R17") (pin "1") (pinfunction "1_1") (pintype "passive"))
      (node (ref "TP27") (pin "1") (pintype "passive"))
    )
    (net (code "30") (name "Net-(Q1-S)") (class "Default")
      (node (ref "Q1") (pin "3") (pinfunction "S_3") (pintype "passive"))
      (node (ref "R19") (pin "2") (pinfunction "2_2") (pintype "passive"))
      (node (ref "R21") (pin "2") (pinfunction "2_2") (pintype "passive"))
      (node (ref "TP41") (pin "1") (pintype "passive"))
    )
    (net (code "31") (name "Net-(Q2-B)") (class "Default")
      (node (ref "C13") (pin "1") (pintype "passive"))
      (node (ref "Q2") (pin "1") (pinfunction "B_1") (pintype "input"))
      (node (ref "R20") (pin "1") (pinfunction "1_1") (pintype "passive"))
      (node (ref "R23") (pin "1") (pinfunction "1_1") (pintype "passive"))
      (node (ref "TP30") (pin "1") (pintype "passive"))
    )
    (net (code "32") (name "Net-(Q2-C)") (class "Default")
      (node (ref "C15") (pin "1") (pintype "passive"))
      (node (ref "Q2") (pin "3") (pinfunction "C_3") (pintype "passive"))
      (node (ref "TP31") (pin "1") (pintype "passive"))
      (node (ref "U1") (pin "1") (pinfunction "OTP_1") (pintype "input"))
    )
    (net (code "33") (name "Net-(Q3-A)") (class "Default")
      (node (ref "Q3") (pin "1") (pinfunction "A_1") (pintype "passive"))
      (node (ref "R22") (pin "1") (pinfunction "1_1") (pintype "passive"))
      (node (ref "R26") (pin "1") (pinfunction "1_1") (pintype "passive"))
      (node (ref "TP33") (pin "1") (pintype "passive"))
    )
    (net (code "34") (name "Net-(R5-Pad2)") (class "Default")
      (node (ref "R5") (pin "2") (pinfunction "2_2") (pintype "passive"))
      (node (ref "R6") (pin "1") (pinfunction "1_1") (pintype "passive"))
      (node (ref "TP8") (pin "1") (pintype "passive"))
    )
    (net (code "35") (name "Net-(R12-Pad1)") (class "Default")
      (node (ref "R12") (pin "1") (pinfunction "1_1") (pintype "passive"))
      (node (ref "R8") (pin "2") (pinfunction "2_2") (pintype "passive"))
      (node (ref "TP16") (pin "1") (pintype "passive"))
    )
    (net (code "36") (name "Net-(R13-Pad2)") (class "Default")
      (node (ref "R13") (pin "2") (pinfunction "2_2") (pintype "passive"))
      (node (ref "R26") (pin "2") (pinfunction "2_2") (pintype "passive"))
      (node (ref "R27") (pin "1") (pinfunction "1_1") (pintype "passive"))
      (node (ref "TP40") (pin "1") (pintype "passive"))
    )
    (net (code "37") (name "Net-(U1-COMP)") (class "Default")
      (node (ref "C12") (pin "1") (pintype "passive"))
      (node (ref "Q3") (pin "4") (pinfunction "C_4") (pintype "passive"))
      (node (ref "TP29") (pin "1") (pintype "passive"))
      (node (ref "U1") (pin "2") (pinfunction "COMP_2") (pintype "passive"))
    )
    (net (code "38") (name "Net-(U1-CS)") (class "Default")
      (node (ref "C11") (pin "2") (pintype "passive"))
      (node (ref "R19") (pin "1") (pinfunction "1_1") (pintype "passive"))
      (node (ref "TP32") (pin "1") (pintype "passive"))
      (node (ref "U1") (pin "3") (pinfunction "CS_3") (pintype "input"))
    )
    (net (code "39") (name "Net-(U1-HV)") (class "Default")
      (node (ref "R12") (pin "2") (pinfunction "2_2") (pintype "passive"))
      (node (ref "TP23") (pin "1") (pintype "passive"))
      (node (ref "U1") (pin "8") (pinfunction "HV_8") (pintype "input"))
    )
    (net (code "40") (name "Net-(U1-OUT)") (class "Default")
      (node (ref "R15") (pin "2") (pinfunction "2_2") (pintype "passive"))
      (node (ref "TP24") (pin "1") (pintype "passive"))
      (node (ref "U1") (pin "5") (pinfunction "OUT_5") (pintype "output"))
    )
    (net (code "41") (name "Net-(U1-VCC)") (class "Default")
      (node (ref "C8") (pin "1") (pintype "passive"))
      (node (ref "C9") (pin "1") (pintype "passive"))
      (node (ref "D3") (pin "K") (pinfunction "K_K") (pintype "passive"))
      (node (ref "TP21") (pin "1") (pintype "passive"))
      (node (ref "U1") (pin "6") (pinfunction "VCC_6") (pintype "power_in"))
    )
    (net (code "42") (name "Net-(U2-CATHODE)") (class "Default")
      (node (ref "C7") (pin "2") (pintype "passive"))
      (node (ref "Q3") (pin "2") (pinfunction "C_2") (pintype "passive"))
      (node (ref "R11") (pin "2") (pinfunction "2_2") (pintype "passive"))
      (node (ref "R22") (pin "2") (pinfunction "2_2") (pintype "passive"))
      (node (ref "TP38") (pin "1") (pintype "passive"))
      (node (ref "U2") (pin "1") (pinfunction "CATHODE_1") (pintype "passive"))
    )
    (net (code "43") (name "Net-(U2-REF)") (class "Default")
      (node (ref "C6") (pin "1") (pintype "passive"))
      (node (ref "C7") (pin "1") (pintype "passive"))
      (node (ref "R27") (pin "2") (pinfunction "2_2") (pintype "passive"))
      (node (ref "R7") (pin "2") (pinfunction "2_2") (pintype "passive"))
      (node (ref "TP39") (pin "1") (pintype "passive"))
      (node (ref "U2") (pin "2") (pinfunction "REF_2") (pintype "input"))
    )
    (net (code "44") (name "unconnected-(FG-Pad1)") (class "Default")
      (node (ref "FG") (pin "1") (pinfunction "1_1") (pintype "passive"))
    )
  )
)
